# J-Link_ARM-OB.net
KiCad netlist of a schematic drawn in Altium Designer
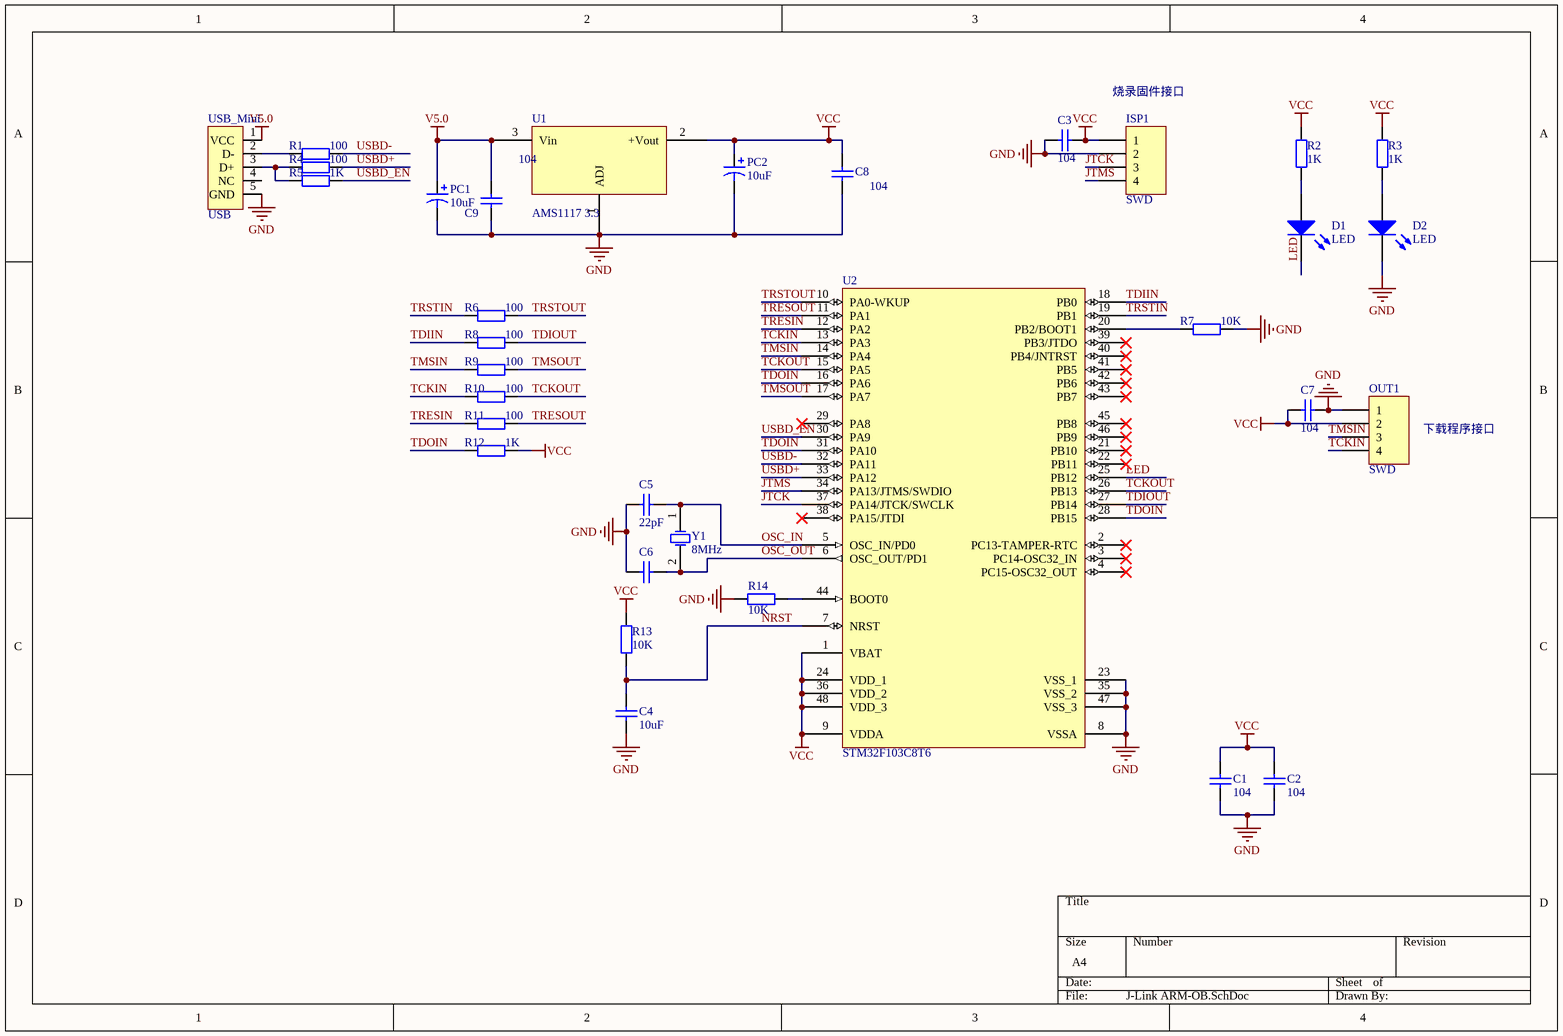
[diagram p0: J-Link ARM-OB.SchDoc]

(export (version "E")
  (design (tool "Eeschema 10.0.6"))
  (components
    (comp (ref "C1")
      (value "104")
      (footprint "C0603")
      (description "Capacitor")
      (fields (field (name "PUBLISHER") "Altium Limited"))
      (libsource (lib "Any") (part "Cap"))
    )
    (comp (ref "C2")
      (value "104")
      (footprint "C0603")
      (description "Capacitor")
      (fields (field (name "PUBLISHER") "Altium Limited"))
      (libsource (lib "Any") (part "Cap"))
    )
    (comp (ref "C3")
      (value "104")
      (footprint "C0603")
      (description "Capacitor")
      (fields (field (name "PUBLISHER") "Altium Limited"))
      (libsource (lib "Any") (part "Cap"))
    )
    (comp (ref "C4")
      (value "10uF")
      (footprint "C0603")
      (description "Capacitor")
      (fields (field (name "PUBLISHER") "Altium Limited"))
      (libsource (lib "Any") (part "Cap"))
    )
    (comp (ref "C5")
      (value "22pF")
      (footprint "C0603")
      (description "Capacitor")
      (fields (field (name "PUBLISHER") "Altium Limited"))
      (libsource (lib "Any") (part "Cap"))
    )
    (comp (ref "C6")
      (value "~")
      (footprint "C0603")
      (description "Capacitor")
      (fields (field (name "PUBLISHER") "Altium Limited"))
      (libsource (lib "Any") (part "Cap"))
    )
    (comp (ref "C7")
      (value "104")
      (footprint "C0603")
      (description "Capacitor")
      (fields (field (name "PUBLISHER") "Altium Limited"))
      (libsource (lib "Any") (part "Cap"))
    )
    (comp (ref "C8")
      (value "104")
      (footprint "C0603")
      (description "Capacitor")
      (fields (field (name "PUBLISHER") "Altium Limited"))
      (libsource (lib "Any") (part "Cap"))
    )
    (comp (ref "C9")
      (value "104")
      (footprint "C0603")
      (description "Capacitor")
      (fields (field (name "PUBLISHER") "Altium Limited"))
      (libsource (lib "Any") (part "Cap"))
    )
    (comp (ref "D1")
      (value "LED")
      (footprint "LED-DIP2")
      (description "Typical RED, GREEN, YELLOW, AMBER GaAs LED")
      (fields (field (name "PUBLISHER") "Altium Limited"))
      (libsource (lib "J-Link ARM-OB_1") (part "LED"))
    )
    (comp (ref "D2")
      (value "LED")
      (footprint "LED-DIP2")
      (description "Typical RED, GREEN, YELLOW, AMBER GaAs LED")
      (fields (field (name "PUBLISHER") "Altium Limited"))
      (libsource (lib "J-Link ARM-OB_1") (part "LED"))
    )
    (comp (ref "ISP1")
      (value "SWD")
      (footprint "HDR1X4")
      (description "Header, 4-Pin")
      (fields (field (name "PUBLISHER") "Altium Limited"))
      (libsource (lib "Miscellaneous Connectors") (part "Header 4"))
    )
    (comp (ref "OUT1")
      (value "SWD")
      (footprint "HDR1X4")
      (description "Header, 4-Pin")
      (fields (field (name "PUBLISHER") "Altium Limited"))
      (libsource (lib "Miscellaneous Connectors") (part "Header 4"))
    )
    (comp (ref "PC1")
      (value "10uF")
      (footprint "C1206A")
      (description "Polarized Capacitor (Surface Mount)")
      (fields (field (name "PUBLISHER") "Altium Limited"))
      (libsource (lib "Miscellaneous Devices") (part "Cap Pol3"))
    )
    (comp (ref "PC2")
      (value "10uF")
      (footprint "C1206A")
      (description "Polarized Capacitor (Surface Mount)")
      (fields (field (name "PUBLISHER") "Altium Limited"))
      (libsource (lib "Miscellaneous Devices") (part "Cap Pol3"))
    )
    (comp (ref "R1")
      (value "100")
      (footprint "R0603")
      (description "Resistor")
      (fields (field (name "PUBLISHER") "Altium Limited"))
      (libsource (lib "Miscellaneous Devices") (part "Res2"))
    )
    (comp (ref "R2")
      (value "1K")
      (footprint "R0603")
      (description "Resistor")
      (fields (field (name "PUBLISHER") "Altium Limited"))
      (libsource (lib "") (part "Res2_1"))
    )
    (comp (ref "R3")
      (value "1K")
      (footprint "R0603")
      (description "Resistor")
      (fields (field (name "PUBLISHER") "Altium Limited"))
      (libsource (lib "") (part "Res2_1"))
    )
    (comp (ref "R4")
      (value "100")
      (footprint "R0603")
      (description "Resistor")
      (fields (field (name "PUBLISHER") "Altium Limited"))
      (libsource (lib "Miscellaneous Devices") (part "Res2"))
    )
    (comp (ref "R5")
      (value "1K")
      (footprint "R0603")
      (description "Resistor")
      (fields (field (name "PUBLISHER") "Altium Limited"))
      (libsource (lib "Miscellaneous Devices") (part "Res2"))
    )
    (comp (ref "R6")
      (value "100")
      (footprint "R0603")
      (description "Resistor")
      (fields (field (name "PUBLISHER") "Altium Limited"))
      (libsource (lib "Miscellaneous Devices") (part "Res2"))
    )
    (comp (ref "R7")
      (value "10K")
      (footprint "R0603")
      (description "Resistor")
      (fields (field (name "PUBLISHER") "Altium Limited"))
      (libsource (lib "Miscellaneous Devices") (part "Res2"))
    )
    (comp (ref "R8")
      (value "100")
      (footprint "R0603")
      (description "Resistor")
      (fields (field (name "PUBLISHER") "Altium Limited"))
      (libsource (lib "Miscellaneous Devices") (part "Res2"))
    )
    (comp (ref "R9")
      (value "100")
      (footprint "R0603")
      (description "Resistor")
      (fields (field (name "PUBLISHER") "Altium Limited"))
      (libsource (lib "Miscellaneous Devices") (part "Res2"))
    )
    (comp (ref "R10")
      (value "100")
      (footprint "R0603")
      (description "Resistor")
      (fields (field (name "PUBLISHER") "Altium Limited"))
      (libsource (lib "Miscellaneous Devices") (part "Res2"))
    )
    (comp (ref "R11")
      (value "100")
      (footprint "R0603")
      (description "Resistor")
      (fields (field (name "PUBLISHER") "Altium Limited"))
      (libsource (lib "Miscellaneous Devices") (part "Res2"))
    )
    (comp (ref "R12")
      (value "1K")
      (footprint "R0603")
      (description "Resistor")
      (fields (field (name "PUBLISHER") "Altium Limited"))
      (libsource (lib "Miscellaneous Devices") (part "Res2"))
    )
    (comp (ref "R13")
      (value "10K")
      (footprint "R0603")
      (description "Resistor")
      (fields (field (name "PUBLISHER") "Altium Limited"))
      (libsource (lib "") (part "Res2_1"))
    )
    (comp (ref "R14")
      (value "10K")
      (footprint "R0603")
      (description "Resistor")
      (fields (field (name "PUBLISHER") "Altium Limited"))
      (libsource (lib "Miscellaneous Devices") (part "Res2"))
    )
    (comp (ref "U1")
      (value "AMS1117 3.3")
      (footprint "SOT-223")
      (libsource (lib "Protel DOS Schematic Libraries") (part "LM117T"))
    )
    (comp (ref "U2")
      (value "STM32F103C8T6")
      (footprint "LQFP48_N")
      (description "STM32 ARM-based 32-bit MCU with 64 Kbytes Flash, 48-pin LQFP, Industrial Temperature")
      (fields (field (name "PUBLISHER") "Altium Limited"))
      (libsource (lib "ST Microcontroller 32-Bit STM32") (part "STM32F103C8T6"))
    )
    (comp (ref "USB_Mini") (value "USB") (footprint "USB Mini") (libsource (lib "战舰板F103库") (part "USB5")))
    (comp (ref "Y1")
      (value "8MHz")
      (footprint "JZ")
      (description "Crystal Oscillator")
      (fields (field (name "PUBLISHER") "Altium Limited"))
      (libsource (lib "Miscellaneous Devices") (part "XTAL"))
    )
  )
  (nets
    (net (code "1") (name "/JTCK") (class "Default")
      (node (ref "ISP1") (pin "3") (pinfunction "3_3") (pintype "passive"))
      (node (ref "U2") (pin "37") (pinfunction "PA14/JTCK/SWCLK_37") (pintype "bidirectional"))
    )
    (net (code "2") (name "/JTMS") (class "Default")
      (node (ref "ISP1") (pin "4") (pinfunction "4_4") (pintype "passive"))
      (node (ref "U2") (pin "34") (pinfunction "PA13/JTMS/SWDIO_34") (pintype "bidirectional"))
    )
    (net (code "3") (name "/LED") (class "Default")
      (node (ref "D1") (pin "2") (pinfunction "K_2") (pintype "passive"))
      (node (ref "U2") (pin "25") (pinfunction "PB12_25") (pintype "bidirectional"))
    )
    (net (code "4") (name "/NRST") (class "Default")
      (node (ref "C4") (pin "1") (pinfunction "1_1") (pintype "passive"))
      (node (ref "R13") (pin "1") (pinfunction "1_1") (pintype "passive"))
      (node (ref "U2") (pin "7") (pinfunction "NRST_7") (pintype "bidirectional"))
    )
    (net (code "5") (name "/OSC_IN") (class "Default")
      (node (ref "C5") (pin "1") (pinfunction "1_1") (pintype "passive"))
      (node (ref "U2") (pin "5") (pinfunction "OSC_IN/PD0_5") (pintype "input"))
      (node (ref "Y1") (pin "1") (pinfunction "OSC1_1") (pintype "passive"))
    )
    (net (code "6") (name "/OSC_OUT") (class "Default")
      (node (ref "C6") (pin "1") (pinfunction "1_1") (pintype "passive"))
      (node (ref "U2") (pin "6") (pinfunction "OSC_OUT/PD1_6") (pintype "output"))
      (node (ref "Y1") (pin "2") (pinfunction "OSC2_2") (pintype "passive"))
    )
    (net (code "7") (name "/TCKIN") (class "Default")
      (node (ref "OUT1") (pin "4") (pinfunction "4_4") (pintype "passive"))
      (node (ref "R10") (pin "1") (pinfunction "1_1") (pintype "passive"))
      (node (ref "U2") (pin "13") (pinfunction "PA3_13") (pintype "bidirectional"))
    )
    (net (code "8") (name "/TCKOUT") (class "Default")
      (node (ref "R10") (pin "2") (pinfunction "2_2") (pintype "passive"))
      (node (ref "U2") (pin "15") (pinfunction "PA5_15") (pintype "bidirectional"))
      (node (ref "U2") (pin "26") (pinfunction "PB13_26") (pintype "bidirectional"))
    )
    (net (code "9") (name "/TDIIN") (class "Default")
      (node (ref "R8") (pin "1") (pinfunction "1_1") (pintype "passive"))
      (node (ref "U2") (pin "18") (pinfunction "PB0_18") (pintype "bidirectional"))
    )
    (net (code "10") (name "/TDIOUT") (class "Default")
      (node (ref "R8") (pin "2") (pinfunction "2_2") (pintype "passive"))
      (node (ref "U2") (pin "27") (pinfunction "PB14_27") (pintype "bidirectional"))
    )
    (net (code "11") (name "/TDOIN") (class "Default")
      (node (ref "R12") (pin "1") (pinfunction "1_1") (pintype "passive"))
      (node (ref "U2") (pin "16") (pinfunction "PA6_16") (pintype "bidirectional"))
      (node (ref "U2") (pin "28") (pinfunction "PB15_28") (pintype "bidirectional"))
      (node (ref "U2") (pin "31") (pinfunction "PA10_31") (pintype "bidirectional"))
    )
    (net (code "12") (name "/TMSIN") (class "Default")
      (node (ref "OUT1") (pin "3") (pinfunction "3_3") (pintype "passive"))
      (node (ref "R9") (pin "1") (pinfunction "1_1") (pintype "passive"))
      (node (ref "U2") (pin "14") (pinfunction "PA4_14") (pintype "bidirectional"))
    )
    (net (code "13") (name "/TMSOUT") (class "Default")
      (node (ref "R9") (pin "2") (pinfunction "2_2") (pintype "passive"))
      (node (ref "U2") (pin "17") (pinfunction "PA7_17") (pintype "bidirectional"))
    )
    (net (code "14") (name "/TRESIN") (class "Default")
      (node (ref "R11") (pin "1") (pinfunction "1_1") (pintype "passive"))
      (node (ref "U2") (pin "12") (pinfunction "PA2_12") (pintype "bidirectional"))
    )
    (net (code "15") (name "/TRESOUT") (class "Default")
      (node (ref "R11") (pin "2") (pinfunction "2_2") (pintype "passive"))
      (node (ref "U2") (pin "11") (pinfunction "PA1_11") (pintype "bidirectional"))
    )
    (net (code "16") (name "/TRSTIN") (class "Default")
      (node (ref "R6") (pin "1") (pinfunction "1_1") (pintype "passive"))
      (node (ref "U2") (pin "19") (pinfunction "PB1_19") (pintype "bidirectional"))
    )
    (net (code "17") (name "/TRSTOUT") (class "Default")
      (node (ref "R6") (pin "2") (pinfunction "2_2") (pintype "passive"))
      (node (ref "U2") (pin "10") (pinfunction "PA0-WKUP_10") (pintype "bidirectional"))
    )
    (net (code "18") (name "/USBD+") (class "Default")
      (node (ref "R4") (pin "2") (pinfunction "2_2") (pintype "passive"))
      (node (ref "U2") (pin "33") (pinfunction "PA12_33") (pintype "bidirectional"))
    )
    (net (code "19") (name "/USBD-") (class "Default")
      (node (ref "R1") (pin "2") (pinfunction "2_2") (pintype "passive"))
      (node (ref "U2") (pin "32") (pinfunction "PA11_32") (pintype "bidirectional"))
    )
    (net (code "20") (name "/USBD_EN") (class "Default")
      (node (ref "R5") (pin "2") (pinfunction "2_2") (pintype "passive"))
      (node (ref "U2") (pin "30") (pinfunction "PA9_30") (pintype "bidirectional"))
    )
    (net (code "21") (name "GND") (class "Default")
      (node (ref "C1") (pin "2") (pinfunction "2_2") (pintype "passive"))
      (node (ref "C2") (pin "2") (pinfunction "2_2") (pintype "passive"))
      (node (ref "C3") (pin "1") (pinfunction "1_1") (pintype "passive"))
      (node (ref "C4") (pin "2") (pinfunction "2_2") (pintype "passive"))
      (node (ref "C5") (pin "2") (pinfunction "2_2") (pintype "passive"))
      (node (ref "C6") (pin "2") (pinfunction "2_2") (pintype "passive"))
      (node (ref "C7") (pin "2") (pinfunction "2_2") (pintype "passive"))
      (node (ref "C8") (pin "2") (pinfunction "2_2") (pintype "passive"))
      (node (ref "C9") (pin "2") (pinfunction "2_2") (pintype "passive"))
      (node (ref "D2") (pin "2") (pinfunction "K_2") (pintype "passive"))
      (node (ref "ISP1") (pin "2") (pinfunction "2_2") (pintype "passive"))
      (node (ref "OUT1") (pin "1") (pinfunction "1_1") (pintype "passive"))
      (node (ref "PC1") (pin "2") (pinfunction "2_2") (pintype "passive"))
      (node (ref "PC2") (pin "2") (pinfunction "2_2") (pintype "passive"))
      (node (ref "R14") (pin "1") (pinfunction "1_1") (pintype "passive"))
      (node (ref "R7") (pin "2") (pinfunction "2_2") (pintype "passive"))
      (node (ref "U1") (pin "1") (pinfunction "ADJ_1") (pintype "passive"))
      (node (ref "U2") (pin "23") (pinfunction "VSS_1_23") (pintype "power_in"))
      (node (ref "U2") (pin "35") (pinfunction "VSS_2_35") (pintype "power_in"))
      (node (ref "U2") (pin "47") (pinfunction "VSS_3_47") (pintype "power_in"))
      (node (ref "U2") (pin "8") (pinfunction "VSSA_8") (pintype "power_in"))
      (node (ref "USB_Mini") (pin "5") (pinfunction "GND_5") (pintype "passive"))
    )
    (net (code "22") (name "Net-(D1-A)") (class "Default")
      (node (ref "D1") (pin "1") (pinfunction "A_1") (pintype "passive"))
      (node (ref "R2") (pin "1") (pinfunction "1_1") (pintype "passive"))
    )
    (net (code "23") (name "Net-(D2-A)") (class "Default")
      (node (ref "D2") (pin "1") (pinfunction "A_1") (pintype "passive"))
      (node (ref "R3") (pin "1") (pinfunction "1_1") (pintype "passive"))
    )
    (net (code "24") (name "Net-(U2-BOOT0)") (class "Default")
      (node (ref "R14") (pin "2") (pinfunction "2_2") (pintype "passive"))
      (node (ref "U2") (pin "44") (pinfunction "BOOT0_44") (pintype "input"))
    )
    (net (code "25") (name "Net-(U2-PB2{slash}BOOT1)") (class "Default")
      (node (ref "R7") (pin "1") (pinfunction "1_1") (pintype "passive"))
      (node (ref "U2") (pin "20") (pinfunction "PB2/BOOT1_20") (pintype "bidirectional"))
    )
    (net (code "26") (name "Net-(USB_Mini-D+)") (class "Default")
      (node (ref "R4") (pin "1") (pinfunction "1_1") (pintype "passive"))
      (node (ref "R5") (pin "1") (pinfunction "1_1") (pintype "passive"))
      (node (ref "USB_Mini") (pin "3") (pinfunction "D+_3") (pintype "passive"))
    )
    (net (code "27") (name "Net-(USB_Mini-D-)") (class "Default")
      (node (ref "R1") (pin "1") (pinfunction "1_1") (pintype "passive"))
      (node (ref "USB_Mini") (pin "2") (pinfunction "D-_2") (pintype "passive"))
    )
    (net (code "28") (name "V5.0") (class "Default")
      (node (ref "C9") (pin "1") (pinfunction "1_1") (pintype "passive"))
      (node (ref "PC1") (pin "1") (pinfunction "1_1") (pintype "passive"))
      (node (ref "U1") (pin "3") (pinfunction "Vin_3") (pintype "passive"))
      (node (ref "USB_Mini") (pin "1") (pinfunction "VCC_1") (pintype "passive"))
    )
    (net (code "29") (name "VCC") (class "Default")
      (node (ref "C1") (pin "1") (pinfunction "1_1") (pintype "passive"))
      (node (ref "C2") (pin "1") (pinfunction "1_1") (pintype "passive"))
      (node (ref "C3") (pin "2") (pinfunction "2_2") (pintype "passive"))
      (node (ref "C7") (pin "1") (pinfunction "1_1") (pintype "passive"))
      (node (ref "C8") (pin "1") (pinfunction "1_1") (pintype "passive"))
      (node (ref "ISP1") (pin "1") (pinfunction "1_1") (pintype "passive"))
      (node (ref "OUT1") (pin "2") (pinfunction "2_2") (pintype "passive"))
      (node (ref "PC2") (pin "1") (pinfunction "1_1") (pintype "passive"))
      (node (ref "R12") (pin "2") (pinfunction "2_2") (pintype "passive"))
      (node (ref "R13") (pin "2") (pinfunction "2_2") (pintype "passive"))
      (node (ref "R2") (pin "2") (pinfunction "2_2") (pintype "passive"))
      (node (ref "R3") (pin "2") (pinfunction "2_2") (pintype "passive"))
      (node (ref "U1") (pin "2") (pinfunction "+Vout_2") (pintype "passive"))
      (node (ref "U2") (pin "1") (pinfunction "VBAT_1") (pintype "power_in"))
      (node (ref "U2") (pin "24") (pinfunction "VDD_1_24") (pintype "power_in"))
      (node (ref "U2") (pin "36") (pinfunction "VDD_2_36") (pintype "power_in"))
      (node (ref "U2") (pin "48") (pinfunction "VDD_3_48") (pintype "power_in"))
      (node (ref "U2") (pin "9") (pinfunction "VDDA_9") (pintype "power_in"))
    )
    (net (code "30") (name "unconnected-(U2-PA8-Pad29)") (class "Default")
      (node (ref "U2") (pin "29") (pinfunction "PA8_29") (pintype "bidirectional+no_connect"))
    )
    (net (code "31") (name "unconnected-(U2-PA15{slash}JTDI-Pad38)") (class "Default")
      (node (ref "U2") (pin "38") (pinfunction "PA15/JTDI_38") (pintype "bidirectional+no_connect"))
    )
    (net (code "32") (name "unconnected-(U2-PB3{slash}JTDO-Pad39)") (class "Default")
      (node (ref "U2") (pin "39") (pinfunction "PB3/JTDO_39") (pintype "bidirectional+no_connect"))
    )
    (net (code "33") (name "unconnected-(U2-PB4{slash}JNTRST-Pad40)") (class "Default")
      (node (ref "U2") (pin "40") (pinfunction "PB4/JNTRST_40") (pintype "bidirectional+no_connect"))
    )
    (net (code "34") (name "unconnected-(U2-PB5-Pad41)") (class "Default")
      (node (ref "U2") (pin "41") (pinfunction "PB5_41") (pintype "bidirectional+no_connect"))
    )
    (net (code "35") (name "unconnected-(U2-PB6-Pad42)") (class "Default")
      (node (ref "U2") (pin "42") (pinfunction "PB6_42") (pintype "bidirectional+no_connect"))
    )
    (net (code "36") (name "unconnected-(U2-PB7-Pad43)") (class "Default")
      (node (ref "U2") (pin "43") (pinfunction "PB7_43") (pintype "bidirectional+no_connect"))
    )
    (net (code "37") (name "unconnected-(U2-PB8-Pad45)") (class "Default")
      (node (ref "U2") (pin "45") (pinfunction "PB8_45") (pintype "bidirectional+no_connect"))
    )
    (net (code "38") (name "unconnected-(U2-PB9-Pad46)") (class "Default")
      (node (ref "U2") (pin "46") (pinfunction "PB9_46") (pintype "bidirectional+no_connect"))
    )
    (net (code "39") (name "unconnected-(U2-PB10-Pad21)") (class "Default")
      (node (ref "U2") (pin "21") (pinfunction "PB10_21") (pintype "bidirectional+no_connect"))
    )
    (net (code "40") (name "unconnected-(U2-PB11-Pad22)") (class "Default")
      (node (ref "U2") (pin "22") (pinfunction "PB11_22") (pintype "bidirectional+no_connect"))
    )
    (net (code "41") (name "unconnected-(U2-PC13-TAMPER-RTC-Pad2)") (class "Default")
      (node (ref "U2") (pin "2") (pinfunction "PC13-TAMPER-RTC_2") (pintype "bidirectional+no_connect"))
    )
    (net (code "42") (name "unconnected-(U2-PC14-OSC32_IN-Pad3)") (class "Default")
      (node (ref "U2") (pin "3") (pinfunction "PC14-OSC32_IN_3") (pintype "bidirectional+no_connect"))
    )
    (net (code "43") (name "unconnected-(U2-PC15-OSC32_OUT-Pad4)") (class "Default")
      (node (ref "U2") (pin "4") (pinfunction "PC15-OSC32_OUT_4") (pintype "bidirectional+no_connect"))
    )
    (net (code "44") (name "unconnected-(USB_Mini-NC-Pad4)") (class "Default")
      (node (ref "USB_Mini") (pin "4") (pinfunction "NC_4") (pintype "passive"))
    )
  )
)
